# AP2112K.net
KiCad netlist of a schematic drawn in Altium Designer
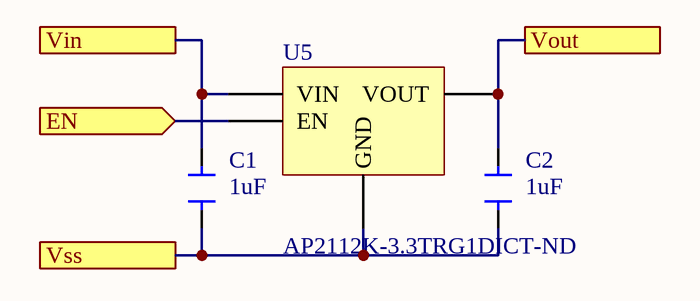
[diagram p0: AP2112K.SchDoc]

(export (version "E")
  (design (tool "Eeschema 10.0.6"))
  (components
    (comp (ref "C1")
      (value "1uF")
      (footprint "CAP_0402")
      (fields (field (name "Comment") "Cap"))
      (libsource (lib "ZGR") (part "Cap"))
    )
    (comp (ref "C2")
      (value "1uF")
      (footprint "CAP_0402")
      (fields (field (name "Comment") "Cap"))
      (libsource (lib "ZGR") (part "Cap"))
    )
    (comp (ref "U5")
      (value "AP2112K-3.3TRG1")
      (footprint "SOT23-5")
      (description "IC REG LINEAR 3.3V 600MA SOT23-5")
      (fields
        (field (name "MANUFACTURER") "Diodes")
        (field (name "SUPPLIER PART NUMBER 1") "AP2112K-3.3TRG1DICT-ND")
      )
      (libsource (lib "ZGR") (part "AP2112K-3.3TRG1"))
    )
  )
  (nets
    (net (code "1") (name "/EN") (class "Default")
      (node (ref "U5") (pin "2") (pinfunction "EN_2") (pintype "passive"))
    )
    (net (code "2") (name "/Vin") (class "Default")
      (node (ref "C1") (pin "1") (pinfunction "1_1") (pintype "passive"))
      (node (ref "U5") (pin "1") (pinfunction "VIN_1") (pintype "power_in"))
    )
    (net (code "3") (name "/Vout") (class "Default")
      (node (ref "C2") (pin "1") (pinfunction "1_1") (pintype "passive"))
      (node (ref "U5") (pin "4") (pinfunction "VOUT_4") (pintype "power_in"))
    )
    (net (code "4") (name "/Vss") (class "Default")
      (node (ref "C1") (pin "2") (pinfunction "2_2") (pintype "passive"))
      (node (ref "C2") (pin "2") (pinfunction "2_2") (pintype "passive"))
      (node (ref "U5") (pin "3") (pinfunction "GND_3") (pintype "power_in"))
    )
  )
)
